# eagle.net
KiCad netlist of a schematic drawn in EAGLE
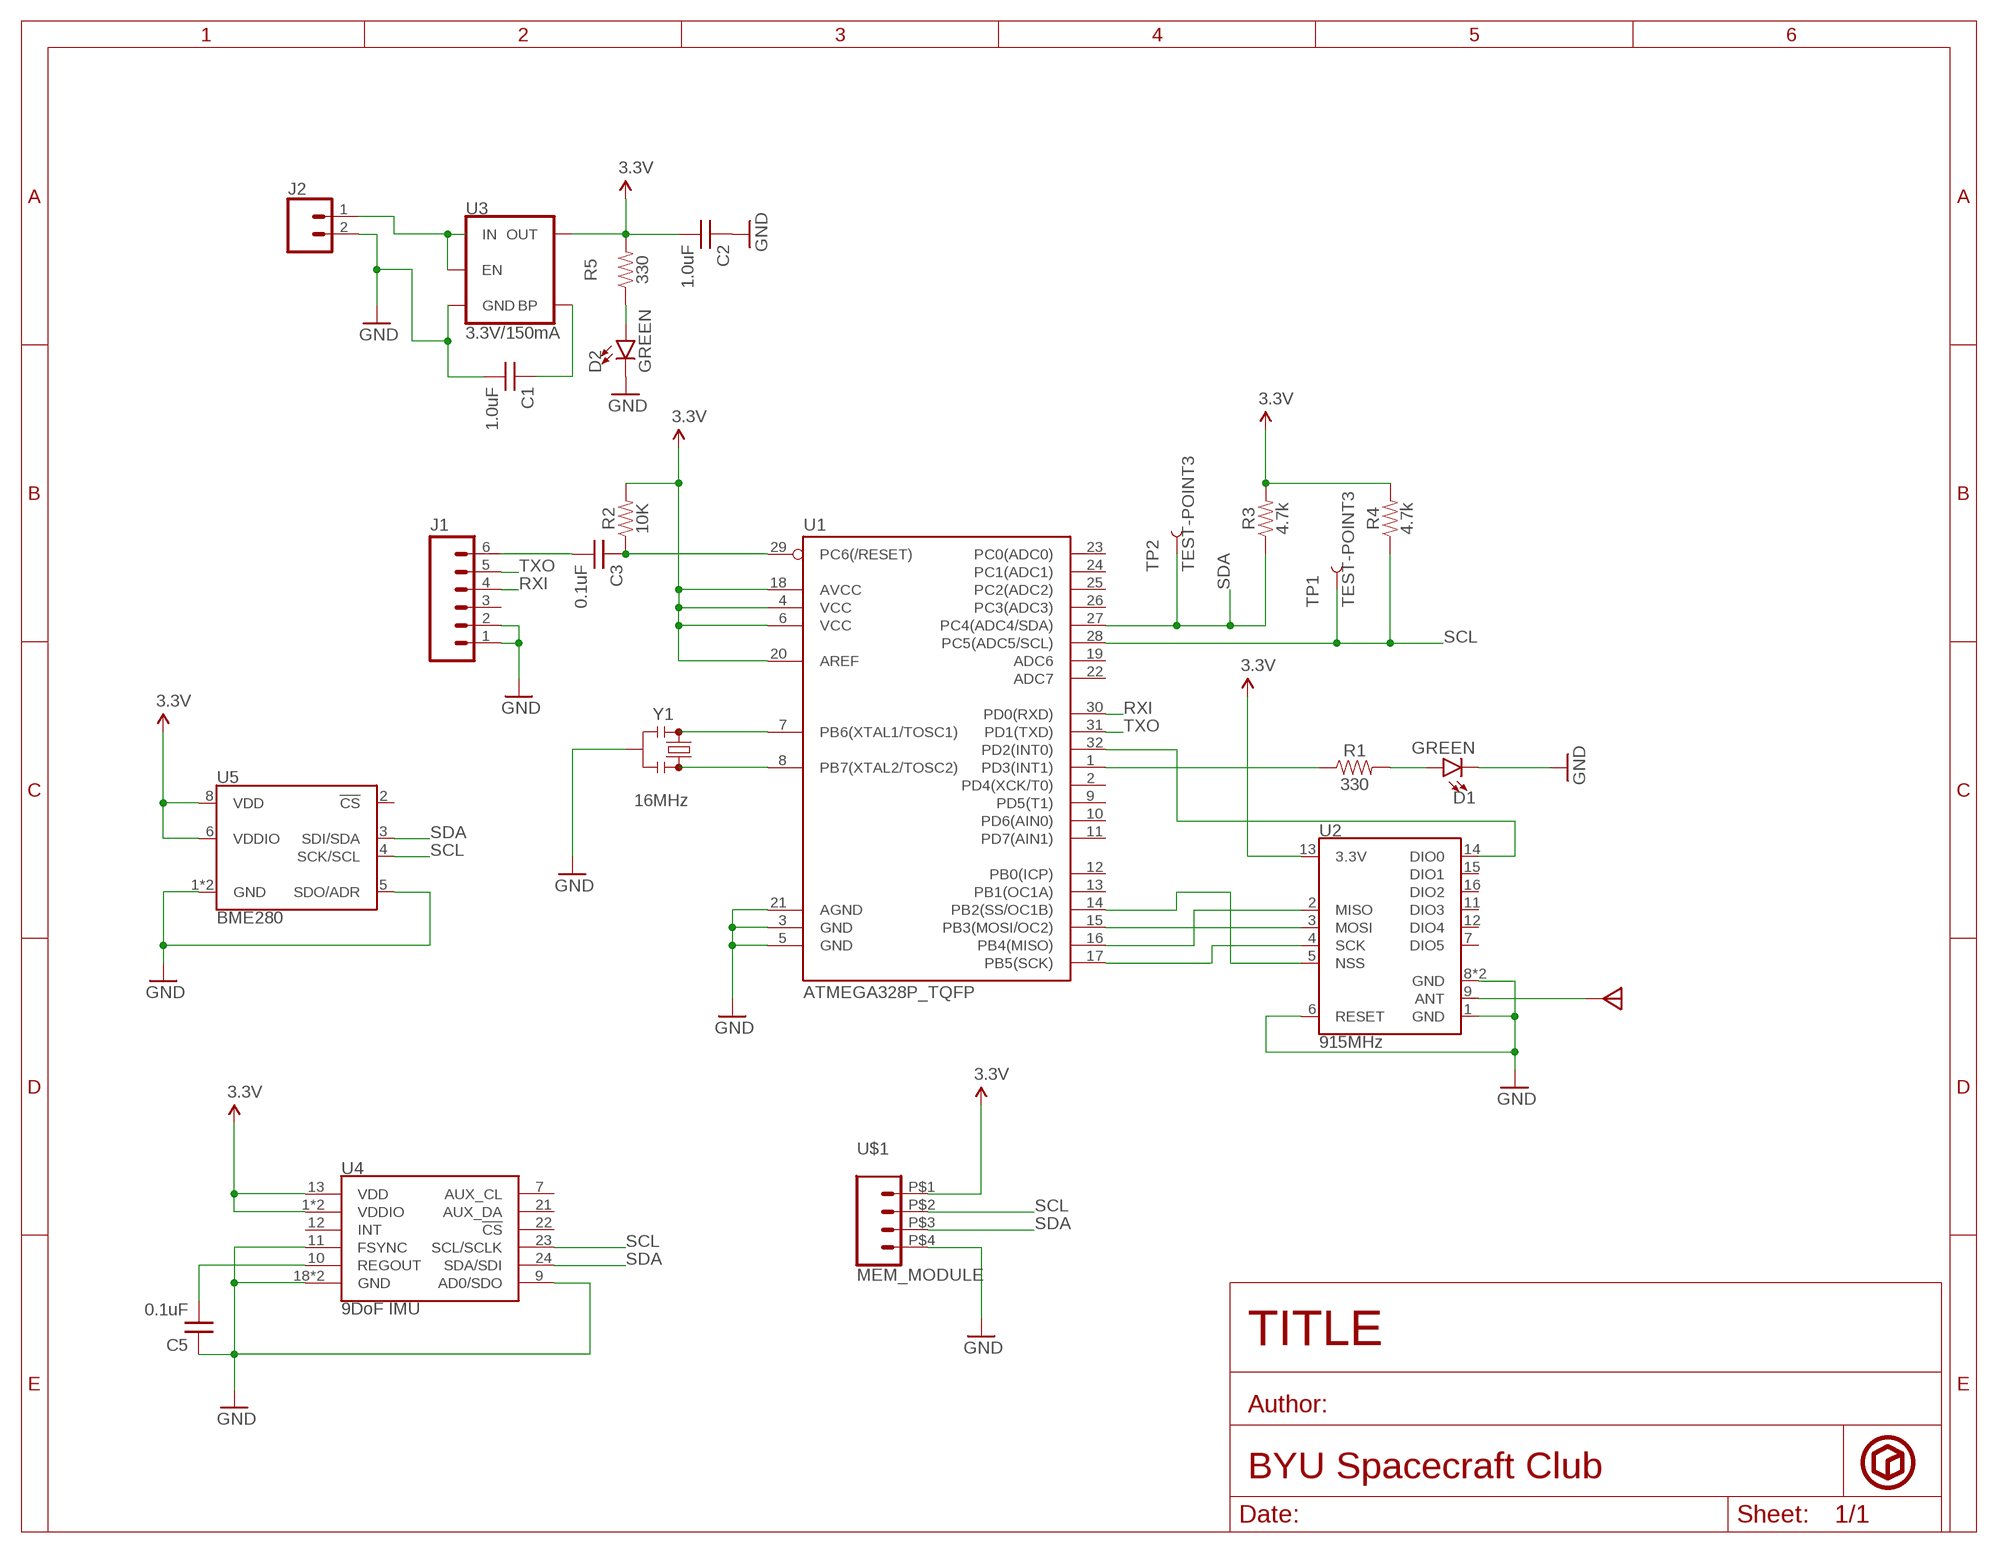
[diagram p0: schematic, sheet 1]

(export (version "E")
  (design (tool "Eeschema 10.0.6"))
  (components
    (comp (ref "ANT1")
      (value "ANTENNA_PAD")
      (footprint "eagle-import:RFM12B-ANTENNA")
      (libsource (lib "eagle-import") (part "ANTENNA_PAD"))
    )
    (comp (ref "C1")
      (value "1.0uF")
      (footprint "eagle-import:0603")
      (libsource (lib "eagle-import") (part "CAPACITOR_1.0UF-0603-16V-10%"))
    )
    (comp (ref "C2")
      (value "1.0uF")
      (footprint "eagle-import:0603")
      (libsource (lib "eagle-import") (part "CAPACITOR_1.0UF-0603-16V-10%"))
    )
    (comp (ref "C3")
      (value "0.1uF")
      (footprint "eagle-import:0603-CAP")
      (libsource (lib "eagle-import") (part "CAPACITOR_0.1UF"))
    )
    (comp (ref "C5")
      (value "0.1uF")
      (footprint "eagle-import:0603-CAP")
      (libsource (lib "eagle-import") (part "CAPACITOR_0.1UF"))
    )
    (comp (ref "D1")
      (value "GREEN")
      (footprint "eagle-import:LED-0603")
      (libsource (lib "eagle-import") (part "LED_GREEN0603"))
    )
    (comp (ref "D2")
      (value "GREEN")
      (footprint "eagle-import:LED-0603")
      (libsource (lib "eagle-import") (part "LED_GREEN0603"))
    )
    (comp (ref "J1")
      (value "CONNECTOR_6PINSILK_FEMALE_PTH")
      (footprint "eagle-import:1X06")
      (libsource (lib "eagle-import") (part "CONNECTOR_6PINSILK_FEMALE_PTH"))
    )
    (comp (ref "J2")
      (value "CONNECTOR_2PIN-JST-2MM-SMT")
      (footprint "eagle-import:JST-2-SMD")
      (libsource (lib "eagle-import") (part "CONNECTOR_2PIN-JST-2MM-SMT"))
    )
    (comp (ref "R1")
      (value "330")
      (footprint "eagle-import:0603")
      (libsource (lib "eagle-import") (part "RESISTOR_330OHM-0603-1/10W-1%"))
    )
    (comp (ref "R2")
      (value "10K")
      (footprint "eagle-import:0603-RES")
      (libsource (lib "eagle-import") (part "RESISTOR_10KOHM0603"))
    )
    (comp (ref "R3")
      (value "4.7k")
      (footprint "eagle-import:0603")
      (libsource (lib "eagle-import") (part "RESISTOR_4.7KOHM-0603-1/10W-1%"))
    )
    (comp (ref "R4")
      (value "4.7k")
      (footprint "eagle-import:0603")
      (libsource (lib "eagle-import") (part "RESISTOR_4.7KOHM-0603-1/10W-1%"))
    )
    (comp (ref "R5")
      (value "330")
      (footprint "eagle-import:0603")
      (libsource (lib "eagle-import") (part "RESISTOR_330OHM-0603-1/10W-1%"))
    )
    (comp (ref "TP1")
      (value "TEST-POINT3")
      (footprint "eagle-import:PAD.03X.03")
      (libsource (lib "eagle-import") (part "TEST-POINT3"))
    )
    (comp (ref "TP2")
      (value "TEST-POINT3")
      (footprint "eagle-import:PAD.03X.03")
      (libsource (lib "eagle-import") (part "TEST-POINT3"))
    )
    (comp (ref "U$1")
      (value "MEM_MODULE")
      (footprint "eagle-import:MEM-HEADERS")
      (libsource (lib "eagle-import") (part "MEM_MODULE"))
    )
    (comp (ref "U1")
      (value "ATMEGA328P_TQFP")
      (footprint "eagle-import:TQFP32-08")
      (libsource (lib "eagle-import") (part "ATMEGA328P_TQFP"))
    )
    (comp (ref "U2")
      (value "915MHz")
      (footprint "eagle-import:RFM69HCW-XXXS2")
      (libsource (lib "eagle-import") (part "RADIO_RFM69HCW-915"))
    )
    (comp (ref "U3")
      (value "3.3V/150mA")
      (footprint "eagle-import:SOT23-5")
      (libsource (lib "eagle-import") (part "VOLTAGE_REGULATOR_MIC52053.3V"))
    )
    (comp (ref "U4")
      (value "9DoF IMU")
      (footprint "eagle-import:QFN24-3X3")
      (libsource (lib "eagle-import") (part "MPU9250"))
    )
    (comp (ref "U5")
      (value "BME280")
      (footprint "eagle-import:LGA-8-2.5X2.5")
      (libsource (lib "eagle-import") (part "BME280"))
    )
    (comp (ref "Y1")
      (value "16MHz")
      (footprint "eagle-import:RESONATOR-SMD-3.2X1.3")
      (libsource (lib "eagle-import") (part "RESONATOR_16MHZSMD_3.2X1.3"))
    )
  )
  (nets
    (net (code "1") (name "/RXI") (class "Default")
      (node (ref "J1") (pin "4") (pinfunction "4_4") (pintype "passive"))
      (node (ref "U1") (pin "30") (pinfunction "PD0(RXD)_30") (pintype "bidirectional"))
    )
    (net (code "2") (name "/SCL") (class "Default")
      (node (ref "R4") (pin "1") (pinfunction "1_1") (pintype "passive"))
      (node (ref "TP1") (pin "P$1") (pinfunction "1_P$1") (pintype "bidirectional"))
      (node (ref "U$1") (pin "P$2") (pinfunction "3_P$2") (pintype "passive"))
      (node (ref "U1") (pin "28") (pinfunction "PC5(ADC5/SCL)_28") (pintype "bidirectional"))
      (node (ref "U4") (pin "23") (pinfunction "SCL/SCLK_23") (pintype "bidirectional"))
      (node (ref "U5") (pin "4") (pinfunction "SCK/SCL_4") (pintype "bidirectional"))
    )
    (net (code "3") (name "/SDA") (class "Default")
      (node (ref "R3") (pin "1") (pinfunction "1_1") (pintype "passive"))
      (node (ref "TP2") (pin "P$1") (pinfunction "1_P$1") (pintype "bidirectional"))
      (node (ref "U$1") (pin "P$3") (pinfunction "2_P$3") (pintype "passive"))
      (node (ref "U1") (pin "27") (pinfunction "PC4(ADC4/SDA)_27") (pintype "bidirectional"))
      (node (ref "U4") (pin "24") (pinfunction "SDA/SDI_24") (pintype "bidirectional"))
      (node (ref "U5") (pin "3") (pinfunction "SDI/SDA_3") (pintype "bidirectional"))
    )
    (net (code "4") (name "/TXO") (class "Default")
      (node (ref "J1") (pin "5") (pinfunction "5_5") (pintype "passive"))
      (node (ref "U1") (pin "31") (pinfunction "PD1(TXD)_31") (pintype "bidirectional"))
    )
    (net (code "5") (name "3.3V") (class "Default")
      (node (ref "C2") (pin "2") (pinfunction "2_2") (pintype "passive"))
      (node (ref "R2") (pin "2") (pinfunction "2_2") (pintype "passive"))
      (node (ref "R3") (pin "2") (pinfunction "2_2") (pintype "passive"))
      (node (ref "R4") (pin "2") (pinfunction "2_2") (pintype "passive"))
      (node (ref "R5") (pin "2") (pinfunction "2_2") (pintype "passive"))
      (node (ref "U$1") (pin "P$1") (pinfunction "4_P$1") (pintype "passive"))
      (node (ref "U1") (pin "18") (pinfunction "AVCC_18") (pintype "bidirectional"))
      (node (ref "U1") (pin "20") (pinfunction "AREF_20") (pintype "bidirectional"))
      (node (ref "U1") (pin "4") (pinfunction "VCC_4") (pintype "bidirectional"))
      (node (ref "U1") (pin "6") (pinfunction "VCC_6") (pintype "bidirectional"))
      (node (ref "U2") (pin "13") (pinfunction "3.3V_13") (pintype "power_in"))
      (node (ref "U3") (pin "5") (pinfunction "OUT_5") (pintype "passive"))
      (node (ref "U4") (pin "1") (pinfunction "VDDIO_1") (pintype "bidirectional"))
      (node (ref "U4") (pin "13") (pinfunction "VDD_13") (pintype "bidirectional"))
      (node (ref "U4") (pin "8") (pinfunction "VDDIO_8") (pintype "bidirectional"))
      (node (ref "U5") (pin "6") (pinfunction "VDDIO_6") (pintype "bidirectional"))
      (node (ref "U5") (pin "8") (pinfunction "VDD_8") (pintype "bidirectional"))
    )
    (net (code "6") (name "GND") (class "Default")
      (node (ref "C1") (pin "2") (pinfunction "2_2") (pintype "passive"))
      (node (ref "C2") (pin "1") (pinfunction "1_1") (pintype "passive"))
      (node (ref "C5") (pin "1") (pinfunction "1_1") (pintype "passive"))
      (node (ref "D1") (pin "C") (pinfunction "C_C") (pintype "passive"))
      (node (ref "D2") (pin "C") (pinfunction "C_C") (pintype "passive"))
      (node (ref "J1") (pin "1") (pinfunction "1_1") (pintype "passive"))
      (node (ref "J1") (pin "2") (pinfunction "2_2") (pintype "passive"))
      (node (ref "J2") (pin "2") (pinfunction "2_2") (pintype "passive"))
      (node (ref "U$1") (pin "P$4") (pinfunction "1_P$4") (pintype "passive"))
      (node (ref "U1") (pin "21") (pinfunction "AGND_21") (pintype "bidirectional"))
      (node (ref "U1") (pin "3") (pinfunction "GND_3") (pintype "bidirectional"))
      (node (ref "U1") (pin "5") (pinfunction "GND_5") (pintype "bidirectional"))
      (node (ref "U2") (pin "1") (pinfunction "GND_1") (pintype "power_in"))
      (node (ref "U2") (pin "10") (pinfunction "GND_10") (pintype "power_in"))
      (node (ref "U2") (pin "6") (pinfunction "RESET_6") (pintype "input"))
      (node (ref "U2") (pin "8") (pinfunction "GND_8") (pintype "power_in"))
      (node (ref "U3") (pin "2") (pinfunction "GND_2") (pintype "input"))
      (node (ref "U4") (pin "11") (pinfunction "FSYNC_11") (pintype "bidirectional"))
      (node (ref "U4") (pin "18") (pinfunction "GND_18") (pintype "bidirectional"))
      (node (ref "U4") (pin "20") (pinfunction "GND_20") (pintype "bidirectional"))
      (node (ref "U4") (pin "9") (pinfunction "AD0/SDO_9") (pintype "bidirectional"))
      (node (ref "U5") (pin "1") (pinfunction "GND_1") (pintype "bidirectional"))
      (node (ref "U5") (pin "5") (pinfunction "SDO/ADR_5") (pintype "bidirectional"))
      (node (ref "U5") (pin "7") (pinfunction "GND_7") (pintype "bidirectional"))
      (node (ref "Y1") (pin "2") (pinfunction "2_2") (pintype "passive"))
    )
    (net (code "7") (name "Net-(ANT1-1)") (class "Default")
      (node (ref "ANT1") (pin "P$1") (pinfunction "1_P$1") (pintype "bidirectional"))
      (node (ref "U2") (pin "9") (pinfunction "ANT_9") (pintype "passive"))
    )
    (net (code "8") (name "Net-(C3-Pad2)") (class "Default")
      (node (ref "C3") (pin "2") (pinfunction "2_2") (pintype "passive"))
      (node (ref "J1") (pin "6") (pinfunction "6_6") (pintype "passive"))
    )
    (net (code "9") (name "Net-(D1-PadA)") (class "Default")
      (node (ref "D1") (pin "A") (pinfunction "A_A") (pintype "passive"))
      (node (ref "R1") (pin "2") (pinfunction "2_2") (pintype "passive"))
    )
    (net (code "10") (name "Net-(D2-PadA)") (class "Default")
      (node (ref "D2") (pin "A") (pinfunction "A_A") (pintype "passive"))
      (node (ref "R5") (pin "1") (pinfunction "1_1") (pintype "passive"))
    )
    (net (code "11") (name "Net-(U1-PB2(SS{slash}OC1B))") (class "Default")
      (node (ref "U1") (pin "14") (pinfunction "PB2(SS/OC1B)_14") (pintype "bidirectional"))
      (node (ref "U2") (pin "5") (pinfunction "NSS_5") (pintype "input"))
    )
    (net (code "12") (name "Net-(U1-PB3(MOSI{slash}OC2))") (class "Default")
      (node (ref "U1") (pin "15") (pinfunction "PB3(MOSI/OC2)_15") (pintype "bidirectional"))
      (node (ref "U2") (pin "3") (pinfunction "MOSI_3") (pintype "input"))
    )
    (net (code "13") (name "Net-(U1-PB4(MISO))") (class "Default")
      (node (ref "U1") (pin "16") (pinfunction "PB4(MISO)_16") (pintype "bidirectional"))
      (node (ref "U2") (pin "2") (pinfunction "MISO_2") (pintype "bidirectional"))
    )
    (net (code "14") (name "Net-(U1-PB5(SCK))") (class "Default")
      (node (ref "U1") (pin "17") (pinfunction "PB5(SCK)_17") (pintype "bidirectional"))
      (node (ref "U2") (pin "4") (pinfunction "SCK_4") (pintype "input"))
    )
    (net (code "15") (name "Net-(U1-PB6(XTAL1{slash}TOSC1))") (class "Default")
      (node (ref "U1") (pin "7") (pinfunction "PB6(XTAL1/TOSC1)_7") (pintype "bidirectional"))
      (node (ref "Y1") (pin "1") (pinfunction "1_1") (pintype "passive"))
    )
    (net (code "16") (name "Net-(U1-PB7(XTAL2{slash}TOSC2))") (class "Default")
      (node (ref "U1") (pin "8") (pinfunction "PB7(XTAL2/TOSC2)_8") (pintype "bidirectional"))
      (node (ref "Y1") (pin "3") (pinfunction "3_3") (pintype "passive"))
    )
    (net (code "17") (name "Net-(U1-PC6({slash}RESET))") (class "Default")
      (node (ref "C3") (pin "1") (pinfunction "1_1") (pintype "passive"))
      (node (ref "R2") (pin "1") (pinfunction "1_1") (pintype "passive"))
      (node (ref "U1") (pin "29") (pinfunction "PC6(/RESET)_29") (pintype "bidirectional"))
    )
    (net (code "18") (name "Net-(U1-PD2(INT0))") (class "Default")
      (node (ref "U1") (pin "32") (pinfunction "PD2(INT0)_32") (pintype "bidirectional"))
      (node (ref "U2") (pin "14") (pinfunction "DIO0_14") (pintype "bidirectional"))
    )
    (net (code "19") (name "Net-(U1-PD3(INT1))") (class "Default")
      (node (ref "R1") (pin "1") (pinfunction "1_1") (pintype "passive"))
      (node (ref "U1") (pin "1") (pinfunction "PD3(INT1)_1") (pintype "bidirectional"))
    )
    (net (code "20") (name "Net-(U3-BP)") (class "Default")
      (node (ref "C1") (pin "1") (pinfunction "1_1") (pintype "passive"))
      (node (ref "U3") (pin "4") (pinfunction "BP_4") (pintype "input"))
    )
    (net (code "21") (name "Net-(U3-EN)") (class "Default")
      (node (ref "J2") (pin "1") (pinfunction "1_1") (pintype "passive"))
      (node (ref "U3") (pin "1") (pinfunction "IN_1") (pintype "input"))
      (node (ref "U3") (pin "3") (pinfunction "EN_3") (pintype "input"))
    )
    (net (code "22") (name "Net-(U4-REGOUT)") (class "Default")
      (node (ref "C5") (pin "2") (pinfunction "2_2") (pintype "passive"))
      (node (ref "U4") (pin "10") (pinfunction "REGOUT_10") (pintype "bidirectional"))
    )
    (net (code "23") (name "unconnected-(J1-Pad3)") (class "Default")
      (node (ref "J1") (pin "3") (pinfunction "3_3") (pintype "passive"))
    )
    (net (code "24") (name "unconnected-(U1-ADC6-Pad19)") (class "Default")
      (node (ref "U1") (pin "19") (pinfunction "ADC6_19") (pintype "bidirectional"))
    )
    (net (code "25") (name "unconnected-(U1-ADC7-Pad22)") (class "Default")
      (node (ref "U1") (pin "22") (pinfunction "ADC7_22") (pintype "bidirectional"))
    )
    (net (code "26") (name "unconnected-(U1-PB0(ICP)-Pad12)") (class "Default")
      (node (ref "U1") (pin "12") (pinfunction "PB0(ICP)_12") (pintype "bidirectional"))
    )
    (net (code "27") (name "unconnected-(U1-PB1(OC1A)-Pad13)") (class "Default")
      (node (ref "U1") (pin "13") (pinfunction "PB1(OC1A)_13") (pintype "bidirectional"))
    )
    (net (code "28") (name "unconnected-(U1-PC0(ADC0)-Pad23)") (class "Default")
      (node (ref "U1") (pin "23") (pinfunction "PC0(ADC0)_23") (pintype "bidirectional"))
    )
    (net (code "29") (name "unconnected-(U1-PC1(ADC1)-Pad24)") (class "Default")
      (node (ref "U1") (pin "24") (pinfunction "PC1(ADC1)_24") (pintype "bidirectional"))
    )
    (net (code "30") (name "unconnected-(U1-PC2(ADC2)-Pad25)") (class "Default")
      (node (ref "U1") (pin "25") (pinfunction "PC2(ADC2)_25") (pintype "bidirectional"))
    )
    (net (code "31") (name "unconnected-(U1-PC3(ADC3)-Pad26)") (class "Default")
      (node (ref "U1") (pin "26") (pinfunction "PC3(ADC3)_26") (pintype "bidirectional"))
    )
    (net (code "32") (name "unconnected-(U1-PD4(XCK{slash}T0)-Pad2)") (class "Default")
      (node (ref "U1") (pin "2") (pinfunction "PD4(XCK/T0)_2") (pintype "bidirectional"))
    )
    (net (code "33") (name "unconnected-(U1-PD5(T1)-Pad9)") (class "Default")
      (node (ref "U1") (pin "9") (pinfunction "PD5(T1)_9") (pintype "bidirectional"))
    )
    (net (code "34") (name "unconnected-(U1-PD6(AIN0)-Pad10)") (class "Default")
      (node (ref "U1") (pin "10") (pinfunction "PD6(AIN0)_10") (pintype "bidirectional"))
    )
    (net (code "35") (name "unconnected-(U1-PD7(AIN1)-Pad11)") (class "Default")
      (node (ref "U1") (pin "11") (pinfunction "PD7(AIN1)_11") (pintype "bidirectional"))
    )
    (net (code "36") (name "unconnected-(U2-DIO1-Pad15)") (class "Default")
      (node (ref "U2") (pin "15") (pinfunction "DIO1_15") (pintype "bidirectional"))
    )
    (net (code "37") (name "unconnected-(U2-DIO2-Pad16)") (class "Default")
      (node (ref "U2") (pin "16") (pinfunction "DIO2_16") (pintype "bidirectional"))
    )
    (net (code "38") (name "unconnected-(U2-DIO3-Pad11)") (class "Default")
      (node (ref "U2") (pin "11") (pinfunction "DIO3_11") (pintype "bidirectional"))
    )
    (net (code "39") (name "unconnected-(U2-DIO4-Pad12)") (class "Default")
      (node (ref "U2") (pin "12") (pinfunction "DIO4_12") (pintype "bidirectional"))
    )
    (net (code "40") (name "unconnected-(U2-DIO5-Pad7)") (class "Default")
      (node (ref "U2") (pin "7") (pinfunction "DIO5_7") (pintype "bidirectional"))
    )
    (net (code "41") (name "unconnected-(U4-AUX_CL-Pad7)") (class "Default")
      (node (ref "U4") (pin "7") (pinfunction "AUX_CL_7") (pintype "bidirectional"))
    )
    (net (code "42") (name "unconnected-(U4-AUX_DA-Pad21)") (class "Default")
      (node (ref "U4") (pin "21") (pinfunction "AUX_DA_21") (pintype "bidirectional"))
    )
    (net (code "43") (name "unconnected-(U4-INT-Pad12)") (class "Default")
      (node (ref "U4") (pin "12") (pinfunction "INT_12") (pintype "bidirectional"))
    )
    (net (code "44") (name "unconnected-(U4-~{CS}-Pad22)") (class "Default")
      (node (ref "U4") (pin "22") (pinfunction "~{CS}_22") (pintype "bidirectional"))
    )
    (net (code "45") (name "unconnected-(U5-~{CS}-Pad2)") (class "Default")
      (node (ref "U5") (pin "2") (pinfunction "~{CS}_2") (pintype "bidirectional"))
    )
  )
)
